# power.net
KiCad netlist of a schematic drawn in Altium Designer
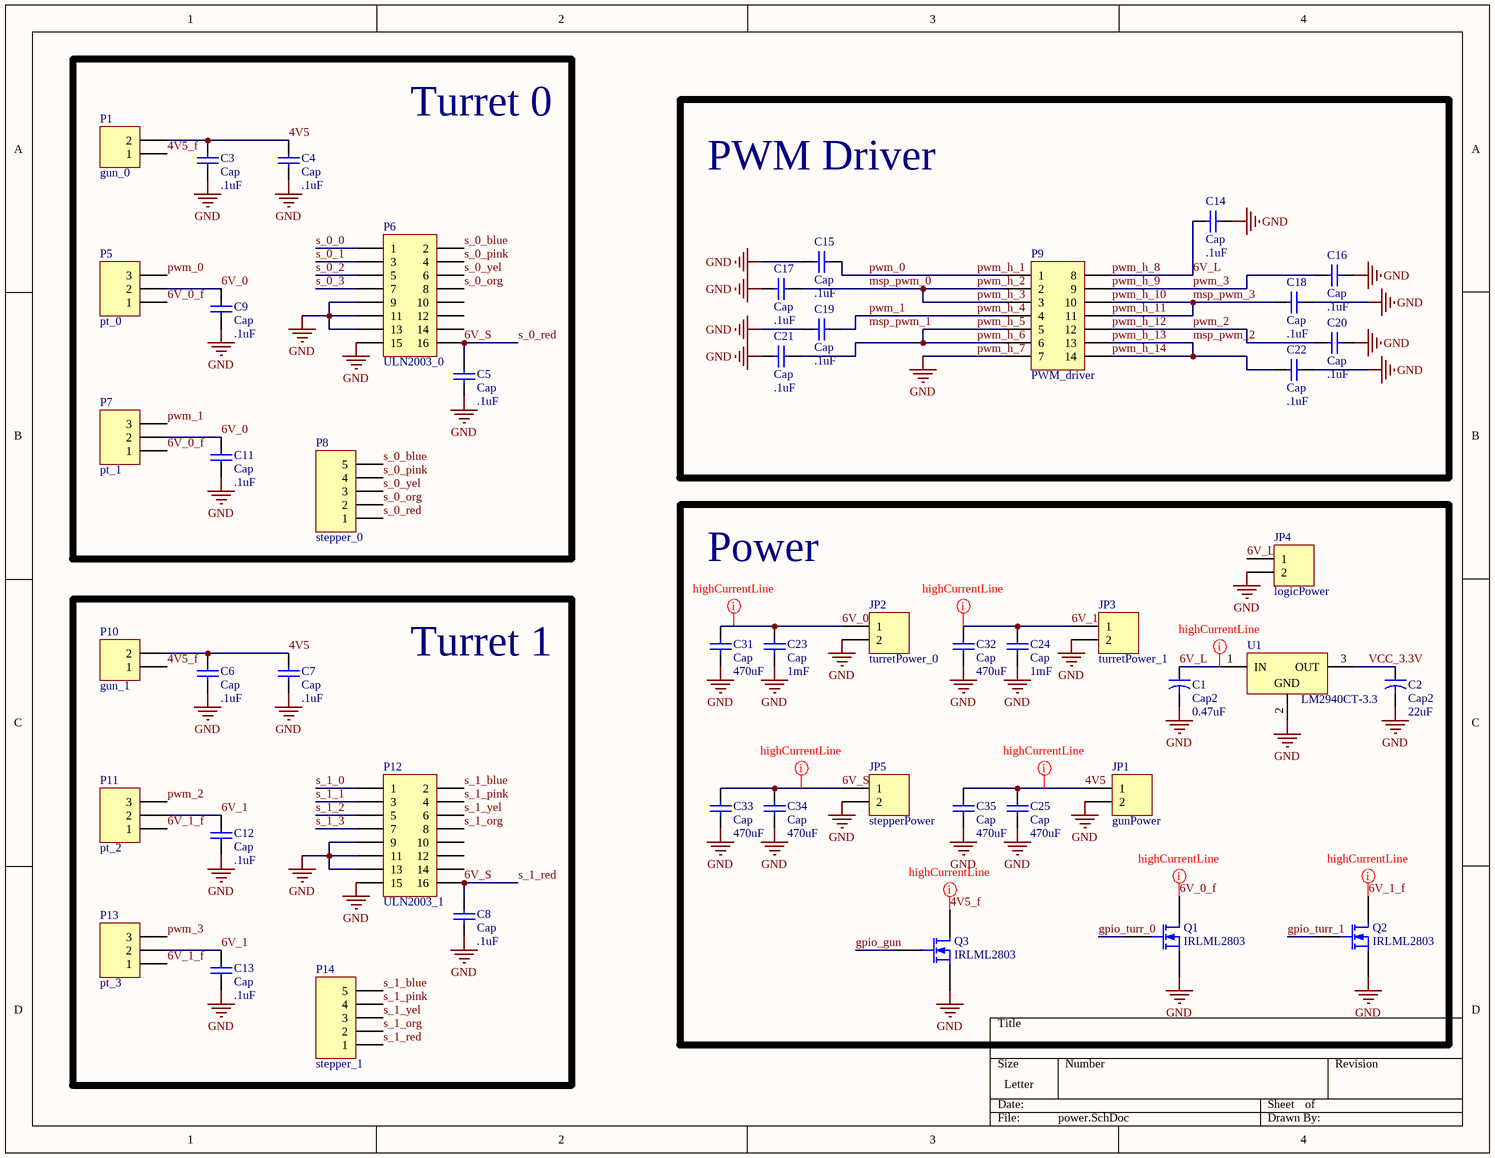
[diagram p0: power.SchDoc]

(export (version "E")
  (design (tool "Eeschema 10.0.6"))
  (components
    (comp (ref "C1")
      (value "Cap2")
      (footprint "RAD-0.1")
      (description "Capacitor")
      (fields (field (name "ALTIUM_VALUE") "0.47uF") (field (name "PUBLISHER") "Altium Limited"))
      (libsource (lib "Miscellaneous Devices") (part "Cap2"))
    )
    (comp (ref "C2")
      (value "Cap2")
      (footprint "RAD-0.1")
      (description "Capacitor")
      (fields (field (name "ALTIUM_VALUE") "22uF") (field (name "PUBLISHER") "Altium Limited"))
      (libsource (lib "Miscellaneous Devices") (part "Cap2"))
    )
    (comp (ref "C3")
      (value "Cap")
      (footprint "RAD-0.1")
      (description "Capacitor")
      (fields (field (name "ALTIUM_VALUE") ".1uF") (field (name "PUBLISHER") "Altium Limited"))
      (libsource (lib "Miscellaneous Devices") (part "Cap"))
    )
    (comp (ref "C4")
      (value "Cap")
      (footprint "RAD-0.1")
      (description "Capacitor")
      (fields (field (name "ALTIUM_VALUE") ".1uF") (field (name "PUBLISHER") "Altium Limited"))
      (libsource (lib "Miscellaneous Devices") (part "Cap"))
    )
    (comp (ref "C5")
      (value "Cap")
      (footprint "RAD-0.1")
      (description "Capacitor")
      (fields (field (name "ALTIUM_VALUE") ".1uF") (field (name "PUBLISHER") "Altium Limited"))
      (libsource (lib "Miscellaneous Devices") (part "Cap"))
    )
    (comp (ref "C6")
      (value "Cap")
      (footprint "RAD-0.1")
      (description "Capacitor")
      (fields (field (name "ALTIUM_VALUE") ".1uF") (field (name "PUBLISHER") "Altium Limited"))
      (libsource (lib "Miscellaneous Devices") (part "Cap"))
    )
    (comp (ref "C7")
      (value "Cap")
      (footprint "RAD-0.1")
      (description "Capacitor")
      (fields (field (name "ALTIUM_VALUE") ".1uF") (field (name "PUBLISHER") "Altium Limited"))
      (libsource (lib "Miscellaneous Devices") (part "Cap"))
    )
    (comp (ref "C8")
      (value "Cap")
      (footprint "RAD-0.1")
      (description "Capacitor")
      (fields (field (name "ALTIUM_VALUE") ".1uF") (field (name "PUBLISHER") "Altium Limited"))
      (libsource (lib "Miscellaneous Devices") (part "Cap"))
    )
    (comp (ref "C9")
      (value "Cap")
      (footprint "RAD-0.1")
      (description "Capacitor")
      (fields (field (name "ALTIUM_VALUE") ".1uF") (field (name "PUBLISHER") "Altium Limited"))
      (libsource (lib "Miscellaneous Devices") (part "Cap"))
    )
    (comp (ref "C11")
      (value "Cap")
      (footprint "RAD-0.1")
      (description "Capacitor")
      (fields (field (name "ALTIUM_VALUE") ".1uF") (field (name "PUBLISHER") "Altium Limited"))
      (libsource (lib "Miscellaneous Devices") (part "Cap"))
    )
    (comp (ref "C12")
      (value "Cap")
      (footprint "RAD-0.1")
      (description "Capacitor")
      (fields (field (name "ALTIUM_VALUE") ".1uF") (field (name "PUBLISHER") "Altium Limited"))
      (libsource (lib "Miscellaneous Devices") (part "Cap"))
    )
    (comp (ref "C13")
      (value "Cap")
      (footprint "RAD-0.1")
      (description "Capacitor")
      (fields (field (name "ALTIUM_VALUE") ".1uF") (field (name "PUBLISHER") "Altium Limited"))
      (libsource (lib "Miscellaneous Devices") (part "Cap"))
    )
    (comp (ref "C14")
      (value "Cap")
      (footprint "RAD-0.1")
      (description "Capacitor")
      (fields (field (name "ALTIUM_VALUE") ".1uF") (field (name "PUBLISHER") "Altium Limited"))
      (libsource (lib "Miscellaneous Devices") (part "Cap"))
    )
    (comp (ref "C15")
      (value "Cap")
      (footprint "RAD-0.1")
      (description "Capacitor")
      (fields (field (name "ALTIUM_VALUE") ".1uF") (field (name "PUBLISHER") "Altium Limited"))
      (libsource (lib "Miscellaneous Devices") (part "Cap"))
    )
    (comp (ref "C16")
      (value "Cap")
      (footprint "RAD-0.1")
      (description "Capacitor")
      (fields (field (name "ALTIUM_VALUE") ".1uF") (field (name "PUBLISHER") "Altium Limited"))
      (libsource (lib "Miscellaneous Devices") (part "Cap"))
    )
    (comp (ref "C17")
      (value "Cap")
      (footprint "RAD-0.1")
      (description "Capacitor")
      (fields (field (name "ALTIUM_VALUE") ".1uF") (field (name "PUBLISHER") "Altium Limited"))
      (libsource (lib "Miscellaneous Devices") (part "Cap"))
    )
    (comp (ref "C18")
      (value "Cap")
      (footprint "RAD-0.1")
      (description "Capacitor")
      (fields (field (name "ALTIUM_VALUE") ".1uF") (field (name "PUBLISHER") "Altium Limited"))
      (libsource (lib "Miscellaneous Devices") (part "Cap"))
    )
    (comp (ref "C19")
      (value "Cap")
      (footprint "RAD-0.1")
      (description "Capacitor")
      (fields (field (name "ALTIUM_VALUE") ".1uF") (field (name "PUBLISHER") "Altium Limited"))
      (libsource (lib "Miscellaneous Devices") (part "Cap"))
    )
    (comp (ref "C20")
      (value "Cap")
      (footprint "RAD-0.1")
      (description "Capacitor")
      (fields (field (name "ALTIUM_VALUE") ".1uF") (field (name "PUBLISHER") "Altium Limited"))
      (libsource (lib "Miscellaneous Devices") (part "Cap"))
    )
    (comp (ref "C21")
      (value "Cap")
      (footprint "RAD-0.1")
      (description "Capacitor")
      (fields (field (name "ALTIUM_VALUE") ".1uF") (field (name "PUBLISHER") "Altium Limited"))
      (libsource (lib "Miscellaneous Devices") (part "Cap"))
    )
    (comp (ref "C22")
      (value "Cap")
      (footprint "RAD-0.1")
      (description "Capacitor")
      (fields (field (name "ALTIUM_VALUE") ".1uF") (field (name "PUBLISHER") "Altium Limited"))
      (libsource (lib "Miscellaneous Devices") (part "Cap"))
    )
    (comp (ref "C23")
      (value "Cap")
      (footprint "RAD-0.1")
      (description "Capacitor")
      (fields (field (name "ALTIUM_VALUE") "1mF") (field (name "PUBLISHER") "Altium Limited"))
      (libsource (lib "Miscellaneous Devices") (part "Cap"))
    )
    (comp (ref "C24")
      (value "Cap")
      (footprint "RAD-0.1")
      (description "Capacitor")
      (fields (field (name "ALTIUM_VALUE") "1mF") (field (name "PUBLISHER") "Altium Limited"))
      (libsource (lib "Miscellaneous Devices") (part "Cap"))
    )
    (comp (ref "C25")
      (value "Cap")
      (footprint "RAD-0.1")
      (description "Capacitor")
      (fields (field (name "ALTIUM_VALUE") "470uF") (field (name "PUBLISHER") "Altium Limited"))
      (libsource (lib "Miscellaneous Devices") (part "Cap"))
    )
    (comp (ref "C31")
      (value "Cap")
      (footprint "RAD-0.1")
      (description "Capacitor")
      (fields (field (name "ALTIUM_VALUE") "470uF") (field (name "PUBLISHER") "Altium Limited"))
      (libsource (lib "Miscellaneous Devices") (part "Cap"))
    )
    (comp (ref "C32")
      (value "Cap")
      (footprint "RAD-0.1")
      (description "Capacitor")
      (fields (field (name "ALTIUM_VALUE") "470uF") (field (name "PUBLISHER") "Altium Limited"))
      (libsource (lib "Miscellaneous Devices") (part "Cap"))
    )
    (comp (ref "C33")
      (value "Cap")
      (footprint "RAD-0.1")
      (description "Capacitor")
      (fields (field (name "ALTIUM_VALUE") "470uF") (field (name "PUBLISHER") "Altium Limited"))
      (libsource (lib "Miscellaneous Devices") (part "Cap"))
    )
    (comp (ref "C34")
      (value "Cap")
      (footprint "RAD-0.1")
      (description "Capacitor")
      (fields (field (name "ALTIUM_VALUE") "470uF") (field (name "PUBLISHER") "Altium Limited"))
      (libsource (lib "Miscellaneous Devices") (part "Cap"))
    )
    (comp (ref "C35")
      (value "Cap")
      (footprint "RAD-0.1")
      (description "Capacitor")
      (fields (field (name "ALTIUM_VALUE") "470uF") (field (name "PUBLISHER") "Altium Limited"))
      (libsource (lib "Miscellaneous Devices") (part "Cap"))
    )
    (comp (ref "JP1")
      (value "gunPower")
      (footprint "CON2screw")
      (libsource (lib "ECE LIB new") (part "Power"))
    )
    (comp (ref "JP2")
      (value "turretPower_0")
      (footprint "CON2screw")
      (libsource (lib "ECE LIB new") (part "Power"))
    )
    (comp (ref "JP3")
      (value "turretPower_1")
      (footprint "CON2screw")
      (libsource (lib "ECE LIB new") (part "Power"))
    )
    (comp (ref "JP4")
      (value "logicPower")
      (footprint "CON2screw")
      (libsource (lib "ECE LIB new") (part "Power"))
    )
    (comp (ref "JP5")
      (value "stepperPower")
      (footprint "CON2screw")
      (libsource (lib "ECE LIB new") (part "Power"))
    )
    (comp (ref "P1")
      (value "gun_0")
      (footprint "HDR1X2")
      (description "Header, 2-Pin")
      (fields (field (name "PUBLISHER") "Altium Limited"))
      (libsource (lib "Miscellaneous Connectors") (part "Header 2"))
    )
    (comp (ref "P5")
      (value "pt_0")
      (footprint "HDR1X3")
      (description "Header, 3-Pin")
      (fields (field (name "PUBLISHER") "Altium Limited"))
      (libsource (lib "Miscellaneous Connectors") (part "Header 3"))
    )
    (comp (ref "P6")
      (value "ULN2003_0")
      (footprint "DIP-16")
      (description "Header, 8-Pin, Dual row")
      (fields (field (name "PUBLISHER") "Altium Limited"))
      (libsource (lib "Miscellaneous Connectors") (part "Header 8X2"))
    )
    (comp (ref "P7")
      (value "pt_1")
      (footprint "HDR1X3")
      (description "Header, 3-Pin")
      (fields (field (name "PUBLISHER") "Altium Limited"))
      (libsource (lib "Miscellaneous Connectors") (part "Header 3"))
    )
    (comp (ref "P8")
      (value "stepper_0")
      (footprint "HDR1X5")
      (description "Header, 5-Pin")
      (fields (field (name "PUBLISHER") "Altium Limited"))
      (libsource (lib "Miscellaneous Connectors") (part "Header 5"))
    )
    (comp (ref "P9")
      (value "PWM_driver")
      (footprint "DIP-14")
      (description "Header, 7-Pin, Dual row")
      (fields (field (name "PUBLISHER") "Altium Limited"))
      (libsource (lib "Miscellaneous Connectors") (part "Header 7X2A"))
    )
    (comp (ref "P10")
      (value "gun_1")
      (footprint "HDR1X2")
      (description "Header, 2-Pin")
      (fields (field (name "PUBLISHER") "Altium Limited"))
      (libsource (lib "Miscellaneous Connectors") (part "Header 2"))
    )
    (comp (ref "P11")
      (value "pt_2")
      (footprint "HDR1X3")
      (description "Header, 3-Pin")
      (fields (field (name "PUBLISHER") "Altium Limited"))
      (libsource (lib "Miscellaneous Connectors") (part "Header 3"))
    )
    (comp (ref "P12")
      (value "ULN2003_1")
      (footprint "DIP-16")
      (description "Header, 8-Pin, Dual row")
      (fields (field (name "PUBLISHER") "Altium Limited"))
      (libsource (lib "Miscellaneous Connectors") (part "Header 8X2"))
    )
    (comp (ref "P13")
      (value "pt_3")
      (footprint "HDR1X3")
      (description "Header, 3-Pin")
      (fields (field (name "PUBLISHER") "Altium Limited"))
      (libsource (lib "Miscellaneous Connectors") (part "Header 3"))
    )
    (comp (ref "P14")
      (value "stepper_1")
      (footprint "HDR1X5")
      (description "Header, 5-Pin")
      (fields (field (name "PUBLISHER") "Altium Limited"))
      (libsource (lib "Miscellaneous Connectors") (part "Header 5"))
    )
    (comp (ref "Q1")
      (value "IRLML2803")
      (footprint "SO-G3")
      (description "N-Channel MOSFET")
      (fields (field (name "PUBLISHER") "Altium Limited"))
      (libsource (lib "ECE LIB new") (part "MOSFET-N"))
    )
    (comp (ref "Q2")
      (value "IRLML2803")
      (footprint "SO-G3")
      (description "N-Channel MOSFET")
      (fields (field (name "PUBLISHER") "Altium Limited"))
      (libsource (lib "ECE LIB new") (part "MOSFET-N"))
    )
    (comp (ref "Q3")
      (value "IRLML2803")
      (footprint "SO-G3")
      (description "N-Channel MOSFET")
      (fields (field (name "PUBLISHER") "Altium Limited"))
      (libsource (lib "ECE LIB new") (part "MOSFET-N"))
    )
    (comp (ref "U1")
      (value "LM2940CT-3.3")
      (footprint "T03B")
      (description "1A Low Dropout Regulator, 3-pin TO-220")
      (fields (field (name "MANUFACTURER") "National Semiconductor"))
      (libsource (lib "ECE LIB new") (part "LM2940CT-5.0"))
    )
  )
  (nets
    (net (code "1") (name "/4V5") (class "Default")
      (node (ref "C25") (pin "2") (pinfunction "2_2") (pintype "passive"))
      (node (ref "C3") (pin "2") (pinfunction "2_2") (pintype "passive"))
      (node (ref "C35") (pin "2") (pinfunction "2_2") (pintype "passive"))
      (node (ref "C4") (pin "1") (pinfunction "1_1") (pintype "passive"))
      (node (ref "C6") (pin "2") (pinfunction "2_2") (pintype "passive"))
      (node (ref "C7") (pin "1") (pinfunction "1_1") (pintype "passive"))
      (node (ref "JP1") (pin "1") (pinfunction "1_1") (pintype "passive"))
      (node (ref "P1") (pin "2") (pinfunction "2_2") (pintype "passive"))
      (node (ref "P10") (pin "2") (pinfunction "2_2") (pintype "passive"))
    )
    (net (code "2") (name "/4V5_f") (class "Default")
      (node (ref "P1") (pin "1") (pinfunction "1_1") (pintype "passive"))
      (node (ref "P10") (pin "1") (pinfunction "1_1") (pintype "passive"))
      (node (ref "Q3") (pin "3") (pinfunction "D_3") (pintype "passive"))
    )
    (net (code "3") (name "/6V_0") (class "Default")
      (node (ref "C11") (pin "2") (pinfunction "2_2") (pintype "passive"))
      (node (ref "C23") (pin "2") (pinfunction "2_2") (pintype "passive"))
      (node (ref "C31") (pin "2") (pinfunction "2_2") (pintype "passive"))
      (node (ref "C9") (pin "2") (pinfunction "2_2") (pintype "passive"))
      (node (ref "JP2") (pin "1") (pinfunction "1_1") (pintype "passive"))
      (node (ref "P5") (pin "2") (pinfunction "2_2") (pintype "passive"))
      (node (ref "P7") (pin "2") (pinfunction "2_2") (pintype "passive"))
    )
    (net (code "4") (name "/6V_0_f") (class "Default")
      (node (ref "P5") (pin "1") (pinfunction "1_1") (pintype "passive"))
      (node (ref "P7") (pin "1") (pinfunction "1_1") (pintype "passive"))
      (node (ref "Q1") (pin "3") (pinfunction "D_3") (pintype "passive"))
    )
    (net (code "5") (name "/6V_1") (class "Default")
      (node (ref "C12") (pin "2") (pinfunction "2_2") (pintype "passive"))
      (node (ref "C13") (pin "2") (pinfunction "2_2") (pintype "passive"))
      (node (ref "C24") (pin "2") (pinfunction "2_2") (pintype "passive"))
      (node (ref "C32") (pin "2") (pinfunction "2_2") (pintype "passive"))
      (node (ref "JP3") (pin "1") (pinfunction "1_1") (pintype "passive"))
      (node (ref "P11") (pin "2") (pinfunction "2_2") (pintype "passive"))
      (node (ref "P13") (pin "2") (pinfunction "2_2") (pintype "passive"))
    )
    (net (code "6") (name "/6V_1_f") (class "Default")
      (node (ref "P11") (pin "1") (pinfunction "1_1") (pintype "passive"))
      (node (ref "P13") (pin "1") (pinfunction "1_1") (pintype "passive"))
      (node (ref "Q2") (pin "3") (pinfunction "D_3") (pintype "passive"))
    )
    (net (code "7") (name "/6V_L") (class "Default")
      (node (ref "C1") (pin "1") (pinfunction "1_1") (pintype "passive"))
      (node (ref "C14") (pin "2") (pinfunction "2_2") (pintype "passive"))
      (node (ref "JP4") (pin "1") (pinfunction "1_1") (pintype "passive"))
      (node (ref "P9") (pin "8") (pinfunction "8_8") (pintype "passive"))
      (node (ref "U1") (pin "1") (pinfunction "IN_1") (pintype "power_in"))
    )
    (net (code "8") (name "/6V_S") (class "Default")
      (node (ref "C33") (pin "2") (pinfunction "2_2") (pintype "passive"))
      (node (ref "C34") (pin "2") (pinfunction "2_2") (pintype "passive"))
      (node (ref "C5") (pin "2") (pinfunction "2_2") (pintype "passive"))
      (node (ref "C8") (pin "2") (pinfunction "2_2") (pintype "passive"))
      (node (ref "JP5") (pin "1") (pinfunction "1_1") (pintype "passive"))
      (node (ref "P12") (pin "16") (pinfunction "16_16") (pintype "passive"))
      (node (ref "P14") (pin "1") (pinfunction "1_1") (pintype "passive"))
      (node (ref "P6") (pin "16") (pinfunction "16_16") (pintype "passive"))
      (node (ref "P8") (pin "1") (pinfunction "1_1") (pintype "passive"))
    )
    (net (code "9") (name "/VCC_3.3V") (class "Default")
      (node (ref "C2") (pin "1") (pinfunction "1_1") (pintype "passive"))
      (node (ref "U1") (pin "3") (pinfunction "OUT_3") (pintype "power_in"))
    )
    (net (code "10") (name "/gpio_gun") (class "Default")
      (node (ref "Q3") (pin "1") (pinfunction "G_1") (pintype "passive"))
    )
    (net (code "11") (name "/gpio_turr_0") (class "Default")
      (node (ref "Q1") (pin "1") (pinfunction "G_1") (pintype "passive"))
    )
    (net (code "12") (name "/gpio_turr_1") (class "Default")
      (node (ref "Q2") (pin "1") (pinfunction "G_1") (pintype "passive"))
    )
    (net (code "13") (name "/msp_pwm_0") (class "Default")
      (node (ref "C17") (pin "1") (pinfunction "1_1") (pintype "passive"))
      (node (ref "P9") (pin "2") (pinfunction "2_2") (pintype "passive"))
      (node (ref "P9") (pin "3") (pinfunction "3_3") (pintype "passive"))
    )
    (net (code "15") (name "/msp_pwm_2") (class "Default")
      (node (ref "C22") (pin "2") (pinfunction "2_2") (pintype "passive"))
      (node (ref "P9") (pin "13") (pinfunction "13_13") (pintype "passive"))
      (node (ref "P9") (pin "14") (pinfunction "14_14") (pintype "passive"))
    )
    (net (code "16") (name "/msp_pwm_3") (class "Default")
      (node (ref "C18") (pin "2") (pinfunction "2_2") (pintype "passive"))
      (node (ref "P9") (pin "10") (pinfunction "10_10") (pintype "passive"))
      (node (ref "P9") (pin "11") (pinfunction "11_11") (pintype "passive"))
    )
    (net (code "17") (name "/pwm_0") (class "Default")
      (node (ref "C15") (pin "1") (pinfunction "1_1") (pintype "passive"))
      (node (ref "P5") (pin "3") (pinfunction "3_3") (pintype "passive"))
      (node (ref "P9") (pin "1") (pinfunction "1_1") (pintype "passive"))
    )
    (net (code "18") (name "/pwm_1") (class "Default")
      (node (ref "C19") (pin "1") (pinfunction "1_1") (pintype "passive"))
      (node (ref "P7") (pin "3") (pinfunction "3_3") (pintype "passive"))
      (node (ref "P9") (pin "4") (pinfunction "4_4") (pintype "passive"))
    )
    (net (code "19") (name "/pwm_2") (class "Default")
      (node (ref "C20") (pin "2") (pinfunction "2_2") (pintype "passive"))
      (node (ref "P11") (pin "3") (pinfunction "3_3") (pintype "passive"))
      (node (ref "P9") (pin "12") (pinfunction "12_12") (pintype "passive"))
    )
    (net (code "20") (name "/pwm_3") (class "Default")
      (node (ref "C16") (pin "2") (pinfunction "2_2") (pintype "passive"))
      (node (ref "P13") (pin "3") (pinfunction "3_3") (pintype "passive"))
      (node (ref "P9") (pin "9") (pinfunction "9_9") (pintype "passive"))
    )
    (net (code "21") (name "/pwm_h_5") (class "Default")
      (node (ref "C21") (pin "1") (pinfunction "1_1") (pintype "passive"))
      (node (ref "P9") (pin "5") (pinfunction "5_5") (pintype "passive"))
      (node (ref "P9") (pin "6") (pinfunction "6_6") (pintype "passive"))
    )
    (net (code "22") (name "/s_0_0") (class "Default")
      (node (ref "P6") (pin "1") (pinfunction "1_1") (pintype "passive"))
    )
    (net (code "23") (name "/s_0_1") (class "Default")
      (node (ref "P6") (pin "3") (pinfunction "3_3") (pintype "passive"))
    )
    (net (code "24") (name "/s_0_2") (class "Default")
      (node (ref "P6") (pin "5") (pinfunction "5_5") (pintype "passive"))
    )
    (net (code "25") (name "/s_0_3") (class "Default")
      (node (ref "P6") (pin "7") (pinfunction "7_7") (pintype "passive"))
    )
    (net (code "26") (name "/s_0_blue") (class "Default")
      (node (ref "P6") (pin "2") (pinfunction "2_2") (pintype "passive"))
      (node (ref "P8") (pin "5") (pinfunction "5_5") (pintype "passive"))
    )
    (net (code "27") (name "/s_0_org") (class "Default")
      (node (ref "P6") (pin "8") (pinfunction "8_8") (pintype "passive"))
      (node (ref "P8") (pin "2") (pinfunction "2_2") (pintype "passive"))
    )
    (net (code "28") (name "/s_0_pink") (class "Default")
      (node (ref "P6") (pin "4") (pinfunction "4_4") (pintype "passive"))
      (node (ref "P8") (pin "4") (pinfunction "4_4") (pintype "passive"))
    )
    (net (code "29") (name "/s_0_yel") (class "Default")
      (node (ref "P6") (pin "6") (pinfunction "6_6") (pintype "passive"))
      (node (ref "P8") (pin "3") (pinfunction "3_3") (pintype "passive"))
    )
    (net (code "30") (name "/s_1_0") (class "Default")
      (node (ref "P12") (pin "1") (pinfunction "1_1") (pintype "passive"))
    )
    (net (code "31") (name "/s_1_1") (class "Default")
      (node (ref "P12") (pin "3") (pinfunction "3_3") (pintype "passive"))
    )
    (net (code "32") (name "/s_1_2") (class "Default")
      (node (ref "P12") (pin "5") (pinfunction "5_5") (pintype "passive"))
    )
    (net (code "33") (name "/s_1_3") (class "Default")
      (node (ref "P12") (pin "7") (pinfunction "7_7") (pintype "passive"))
    )
    (net (code "34") (name "/s_1_blue") (class "Default")
      (node (ref "P12") (pin "2") (pinfunction "2_2") (pintype "passive"))
      (node (ref "P14") (pin "5") (pinfunction "5_5") (pintype "passive"))
    )
    (net (code "35") (name "/s_1_org") (class "Default")
      (node (ref "P12") (pin "8") (pinfunction "8_8") (pintype "passive"))
      (node (ref "P14") (pin "2") (pinfunction "2_2") (pintype "passive"))
    )
    (net (code "36") (name "/s_1_pink") (class "Default")
      (node (ref "P12") (pin "4") (pinfunction "4_4") (pintype "passive"))
      (node (ref "P14") (pin "4") (pinfunction "4_4") (pintype "passive"))
    )
    (net (code "37") (name "/s_1_yel") (class "Default")
      (node (ref "P12") (pin "6") (pinfunction "6_6") (pintype "passive"))
      (node (ref "P14") (pin "3") (pinfunction "3_3") (pintype "passive"))
    )
    (net (code "38") (name "GND") (class "Default")
      (node (ref "C1") (pin "2") (pinfunction "2_2") (pintype "passive"))
      (node (ref "C11") (pin "1") (pinfunction "1_1") (pintype "passive"))
      (node (ref "C12") (pin "1") (pinfunction "1_1") (pintype "passive"))
      (node (ref "C13") (pin "1") (pinfunction "1_1") (pintype "passive"))
      (node (ref "C14") (pin "1") (pinfunction "1_1") (pintype "passive"))
      (node (ref "C15") (pin "2") (pinfunction "2_2") (pintype "passive"))
      (node (ref "C16") (pin "1") (pinfunction "1_1") (pintype "passive"))
      (node (ref "C17") (pin "2") (pinfunction "2_2") (pintype "passive"))
      (node (ref "C18") (pin "1") (pinfunction "1_1") (pintype "passive"))
      (node (ref "C19") (pin "2") (pinfunction "2_2") (pintype "passive"))
      (node (ref "C2") (pin "2") (pinfunction "2_2") (pintype "passive"))
      (node (ref "C20") (pin "1") (pinfunction "1_1") (pintype "passive"))
      (node (ref "C21") (pin "2") (pinfunction "2_2") (pintype "passive"))
      (node (ref "C22") (pin "1") (pinfunction "1_1") (pintype "passive"))
      (node (ref "C23") (pin "1") (pinfunction "1_1") (pintype "passive"))
      (node (ref "C24") (pin "1") (pinfunction "1_1") (pintype "passive"))
      (node (ref "C25") (pin "1") (pinfunction "1_1") (pintype "passive"))
      (node (ref "C3") (pin "1") (pinfunction "1_1") (pintype "passive"))
      (node (ref "C31") (pin "1") (pinfunction "1_1") (pintype "passive"))
      (node (ref "C32") (pin "1") (pinfunction "1_1") (pintype "passive"))
      (node (ref "C33") (pin "1") (pinfunction "1_1") (pintype "passive"))
      (node (ref "C34") (pin "1") (pinfunction "1_1") (pintype "passive"))
      (node (ref "C35") (pin "1") (pinfunction "1_1") (pintype "passive"))
      (node (ref "C4") (pin "2") (pinfunction "2_2") (pintype "passive"))
      (node (ref "C5") (pin "1") (pinfunction "1_1") (pintype "passive"))
      (node (ref "C6") (pin "1") (pinfunction "1_1") (pintype "passive"))
      (node (ref "C7") (pin "2") (pinfunction "2_2") (pintype "passive"))
      (node (ref "C8") (pin "1") (pinfunction "1_1") (pintype "passive"))
      (node (ref "C9") (pin "1") (pinfunction "1_1") (pintype "passive"))
      (node (ref "JP1") (pin "2") (pinfunction "2_2") (pintype "passive"))
      (node (ref "JP2") (pin "2") (pinfunction "2_2") (pintype "passive"))
      (node (ref "JP3") (pin "2") (pinfunction "2_2") (pintype "passive"))
      (node (ref "JP4") (pin "2") (pinfunction "2_2") (pintype "passive"))
      (node (ref "JP5") (pin "2") (pinfunction "2_2") (pintype "passive"))
      (node (ref "P12") (pin "11") (pinfunction "11_11") (pintype "passive"))
      (node (ref "P12") (pin "13") (pinfunction "13_13") (pintype "passive"))
      (node (ref "P12") (pin "15") (pinfunction "15_15") (pintype "passive"))
      (node (ref "P12") (pin "9") (pinfunction "9_9") (pintype "passive"))
      (node (ref "P6") (pin "11") (pinfunction "11_11") (pintype "passive"))
      (node (ref "P6") (pin "13") (pinfunction "13_13") (pintype "passive"))
      (node (ref "P6") (pin "15") (pinfunction "15_15") (pintype "passive"))
      (node (ref "P6") (pin "9") (pinfunction "9_9") (pintype "passive"))
      (node (ref "P9") (pin "7") (pinfunction "7_7") (pintype "passive"))
      (node (ref "Q1") (pin "2") (pinfunction "S_2") (pintype "passive"))
      (node (ref "Q2") (pin "2") (pinfunction "S_2") (pintype "passive"))
      (node (ref "Q3") (pin "2") (pinfunction "S_2") (pintype "passive"))
      (node (ref "U1") (pin "2") (pinfunction "GND_2") (pintype "power_in"))
    )
    (net (code "39") (name "unconnected-(P6-Pad10)") (class "Default")
      (node (ref "P6") (pin "10") (pinfunction "10_10") (pintype "passive"))
    )
    (net (code "40") (name "unconnected-(P6-Pad12)") (class "Default")
      (node (ref "P6") (pin "12") (pinfunction "12_12") (pintype "passive"))
    )
    (net (code "41") (name "unconnected-(P6-Pad14)") (class "Default")
      (node (ref "P6") (pin "14") (pinfunction "14_14") (pintype "passive"))
    )
    (net (code "42") (name "unconnected-(P12-Pad10)") (class "Default")
      (node (ref "P12") (pin "10") (pinfunction "10_10") (pintype "passive"))
    )
    (net (code "43") (name "unconnected-(P12-Pad12)") (class "Default")
      (node (ref "P12") (pin "12") (pinfunction "12_12") (pintype "passive"))
    )
    (net (code "44") (name "unconnected-(P12-Pad14)") (class "Default")
      (node (ref "P12") (pin "14") (pinfunction "14_14") (pintype "passive"))
    )
  )
)
